# SCH_New-Project_2024-06-10.net
KiCad netlist of a schematic drawn in EasyEDA
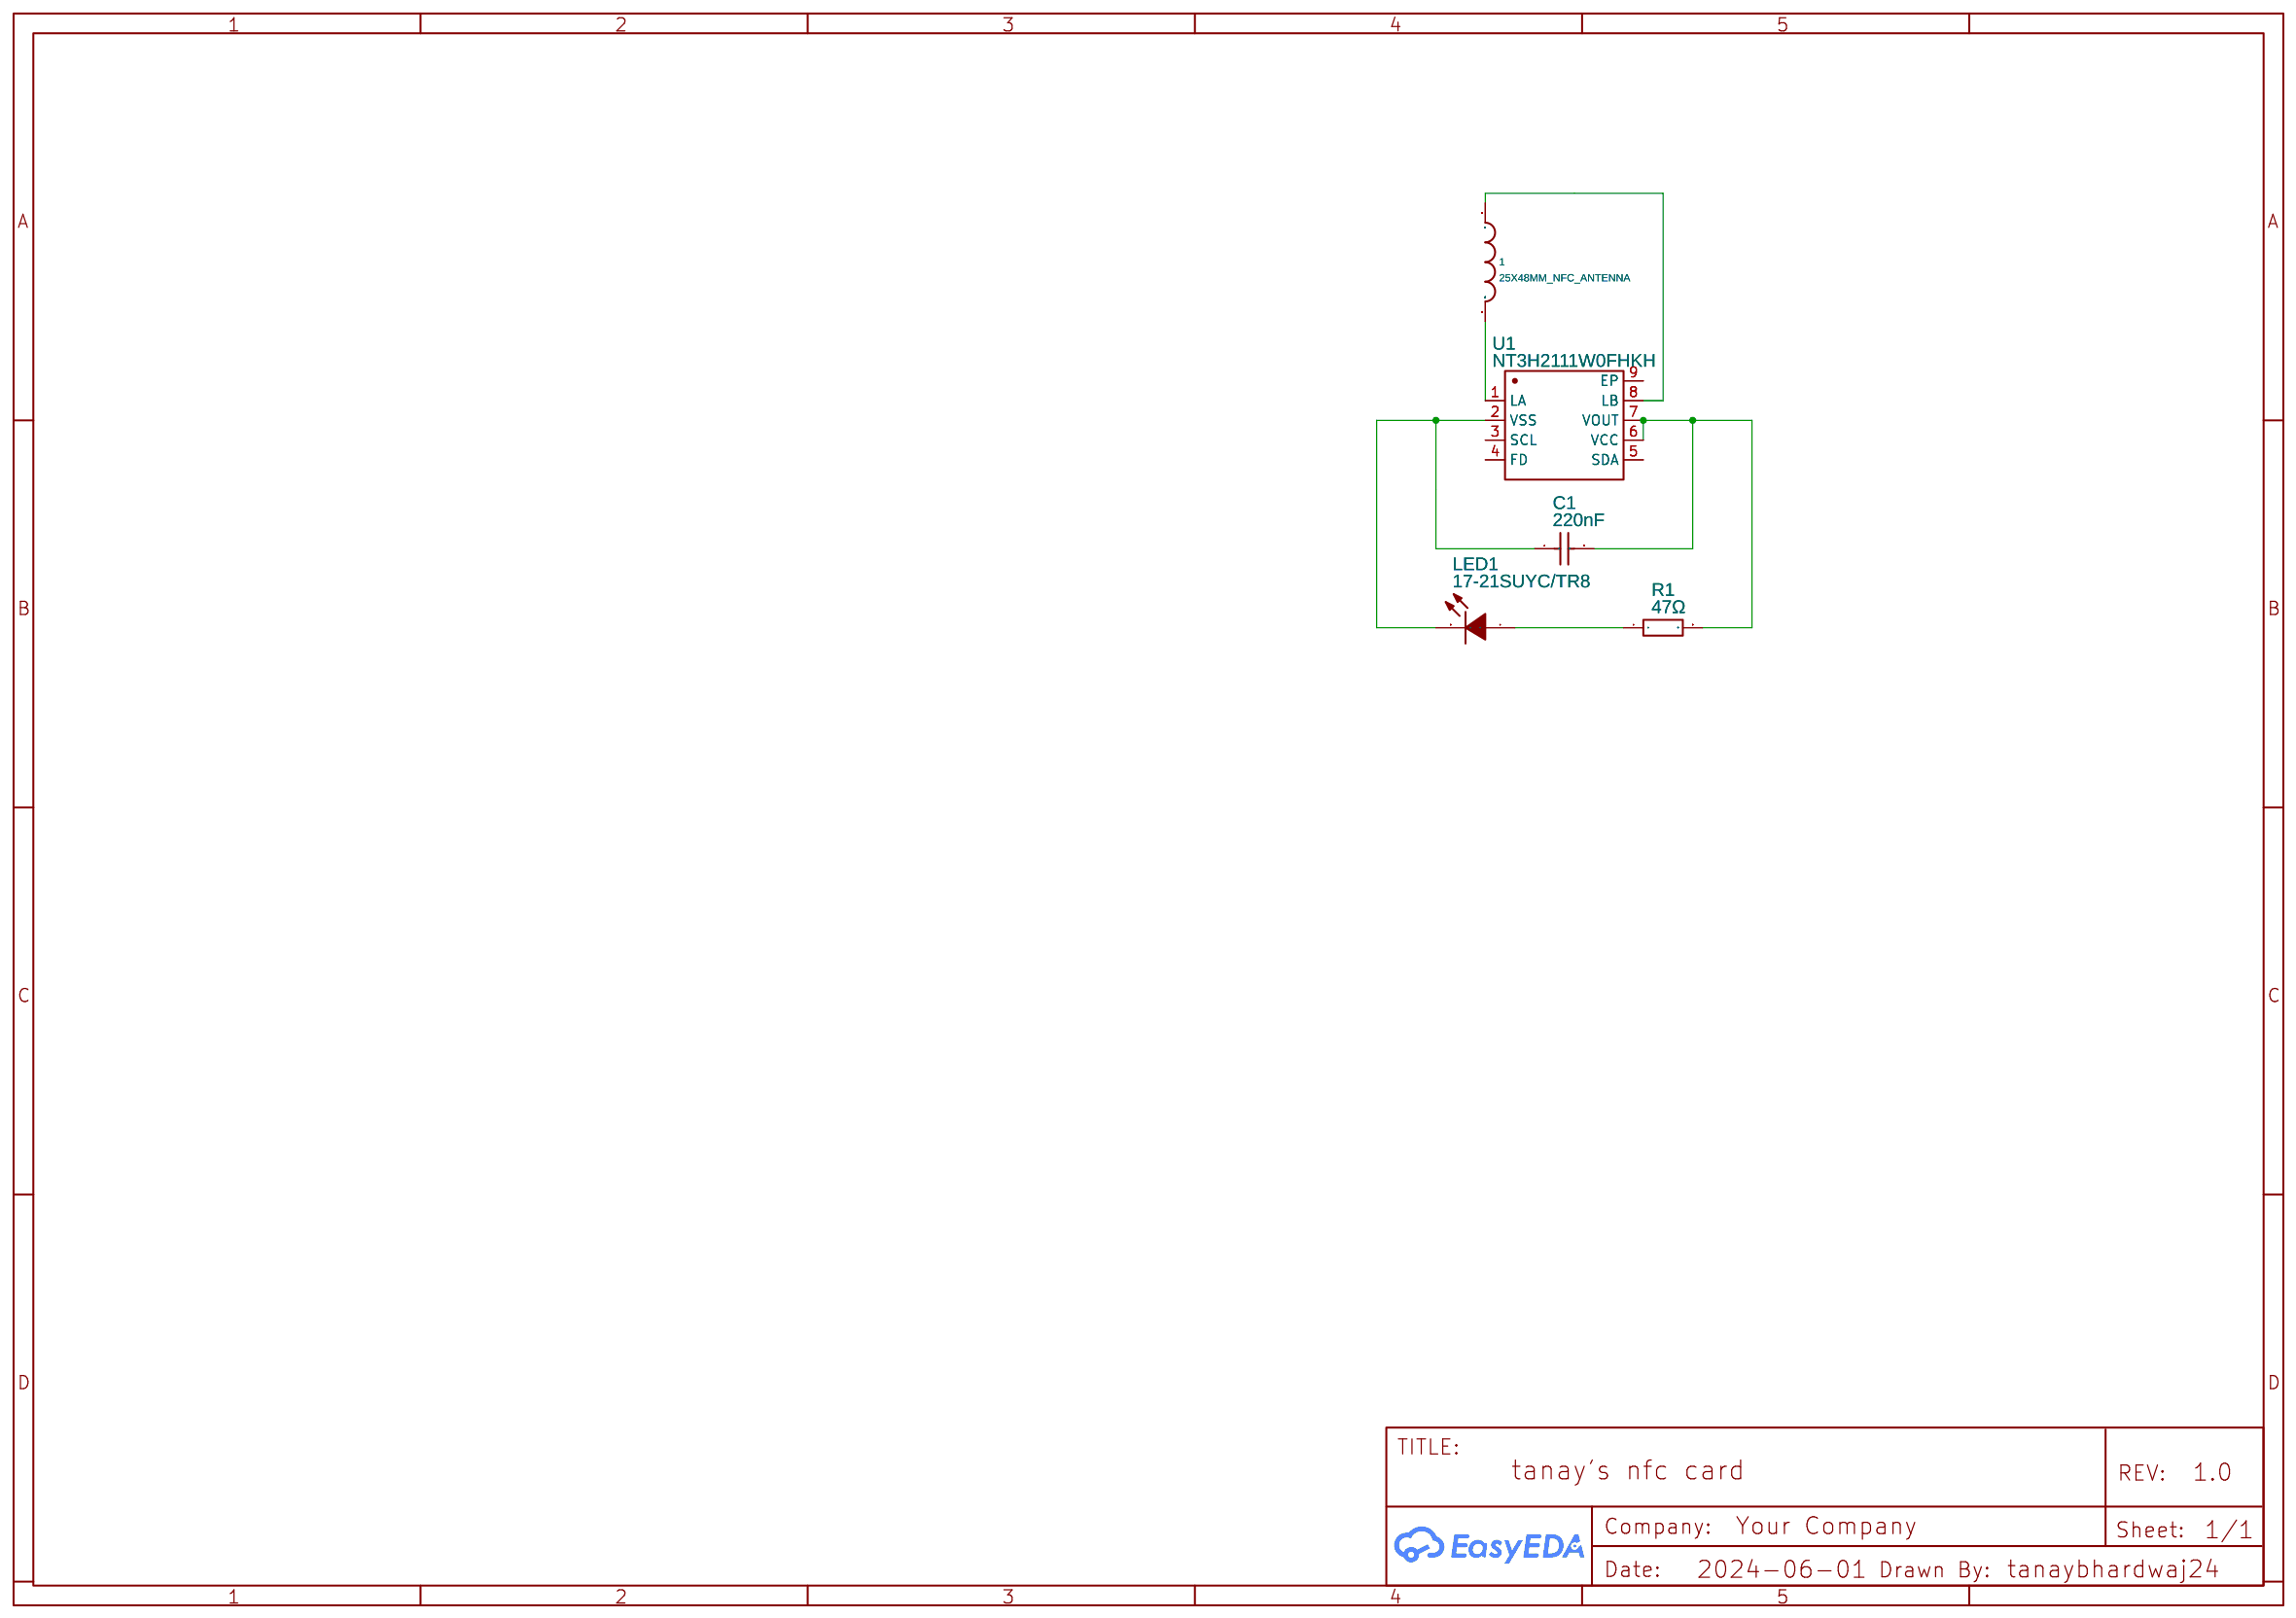
[diagram p0: schematic sheet]

(export (version "E")
  (design (tool "Eeschema 10.0.6"))
  (components
    (comp (ref "1") (value "25X48MM_NFC_ANTENNA") (libsource (lib "") (part "25X48MM_NFC_ANTENNA")))
    (comp (ref "C1")
      (value "220nF")
      (fields
        (field (name "Manufacturer Part") "CL10B224KA8NNNC")
        (field (name "Manufacturer") "SAMSUNG(三星)")
      )
      (libsource (lib "") (part "CL10B224KA8NNNC"))
    )
    (comp (ref "LED1")
      (value "17-21SUYC/TR8")
      (fields (field (name "Manufacturer Part") "KT-0805黄灯") (field (name "Manufacturer") "KENTO"))
      (libsource (lib "") (part "17-21SUYC/TR8"))
    )
    (comp (ref "R1")
      (value "47Ω")
      (fields
        (field (name "Manufacturer Part") "0603WAF470JT5E")
        (field (name "Manufacturer") "UNI-ROYAL(厚声)")
      )
      (libsource (lib "") (part "0603WAF470JT5E"))
    )
    (comp (ref "U1")
      (value "NT3H2111W0FHKH")
      (fields (field (name "Manufacturer") "NXP(恩智浦)"))
      (libsource (lib "") (part "NT3H2111W0FHKH"))
    )
  )
  (nets
    (net (code "1") (name "Net-(LED1-+)") (class "Default")
      (node (ref "LED1") (pin "1") (pinfunction "+_1") (pintype "unspecified"))
      (node (ref "R1") (pin "1") (pinfunction "1_1") (pintype "input"))
    )
    (net (code "2") (name "Net-(LED1--)") (class "Default")
      (node (ref "C1") (pin "1") (pinfunction "1_1") (pintype "input"))
      (node (ref "LED1") (pin "2") (pinfunction "-_2") (pintype "unspecified"))
      (node (ref "U1") (pin "2") (pinfunction "VSS_2") (pintype "unspecified"))
    )
    (net (code "3") (name "Net-(U1-LA)") (class "Default")
      (node (ref "1") (pin "P$2") (pinfunction "P$2_P$2") (pintype "bidirectional"))
      (node (ref "U1") (pin "1") (pinfunction "LA_1") (pintype "unspecified"))
    )
    (net (code "4") (name "Net-(U1-LB)") (class "Default")
      (node (ref "1") (pin "P$1") (pinfunction "P$1_P$1") (pintype "bidirectional"))
      (node (ref "U1") (pin "8") (pinfunction "LB_8") (pintype "unspecified"))
    )
    (net (code "5") (name "Net-(U1-VCC)") (class "Default")
      (node (ref "C1") (pin "2") (pinfunction "2_2") (pintype "input"))
      (node (ref "R1") (pin "2") (pinfunction "2_2") (pintype "input"))
      (node (ref "U1") (pin "6") (pinfunction "VCC_6") (pintype "unspecified"))
      (node (ref "U1") (pin "7") (pinfunction "VOUT_7") (pintype "unspecified"))
    )
    (net (code "6") (name "unconnected-(U1-EP-Pad9)") (class "Default")
      (node (ref "U1") (pin "9") (pinfunction "EP_9") (pintype "unspecified"))
    )
    (net (code "7") (name "unconnected-(U1-FD-Pad4)") (class "Default")
      (node (ref "U1") (pin "4") (pinfunction "FD_4") (pintype "unspecified"))
    )
    (net (code "8") (name "unconnected-(U1-SCL-Pad3)") (class "Default")
      (node (ref "U1") (pin "3") (pinfunction "SCL_3") (pintype "unspecified"))
    )
    (net (code "9") (name "unconnected-(U1-SDA-Pad5)") (class "Default")
      (node (ref "U1") (pin "5") (pinfunction "SDA_5") (pintype "unspecified"))
    )
  )
)
